# SCH_sensor-de-n_vel_2026-06-17.net
KiCad netlist of a schematic drawn in EasyEDA
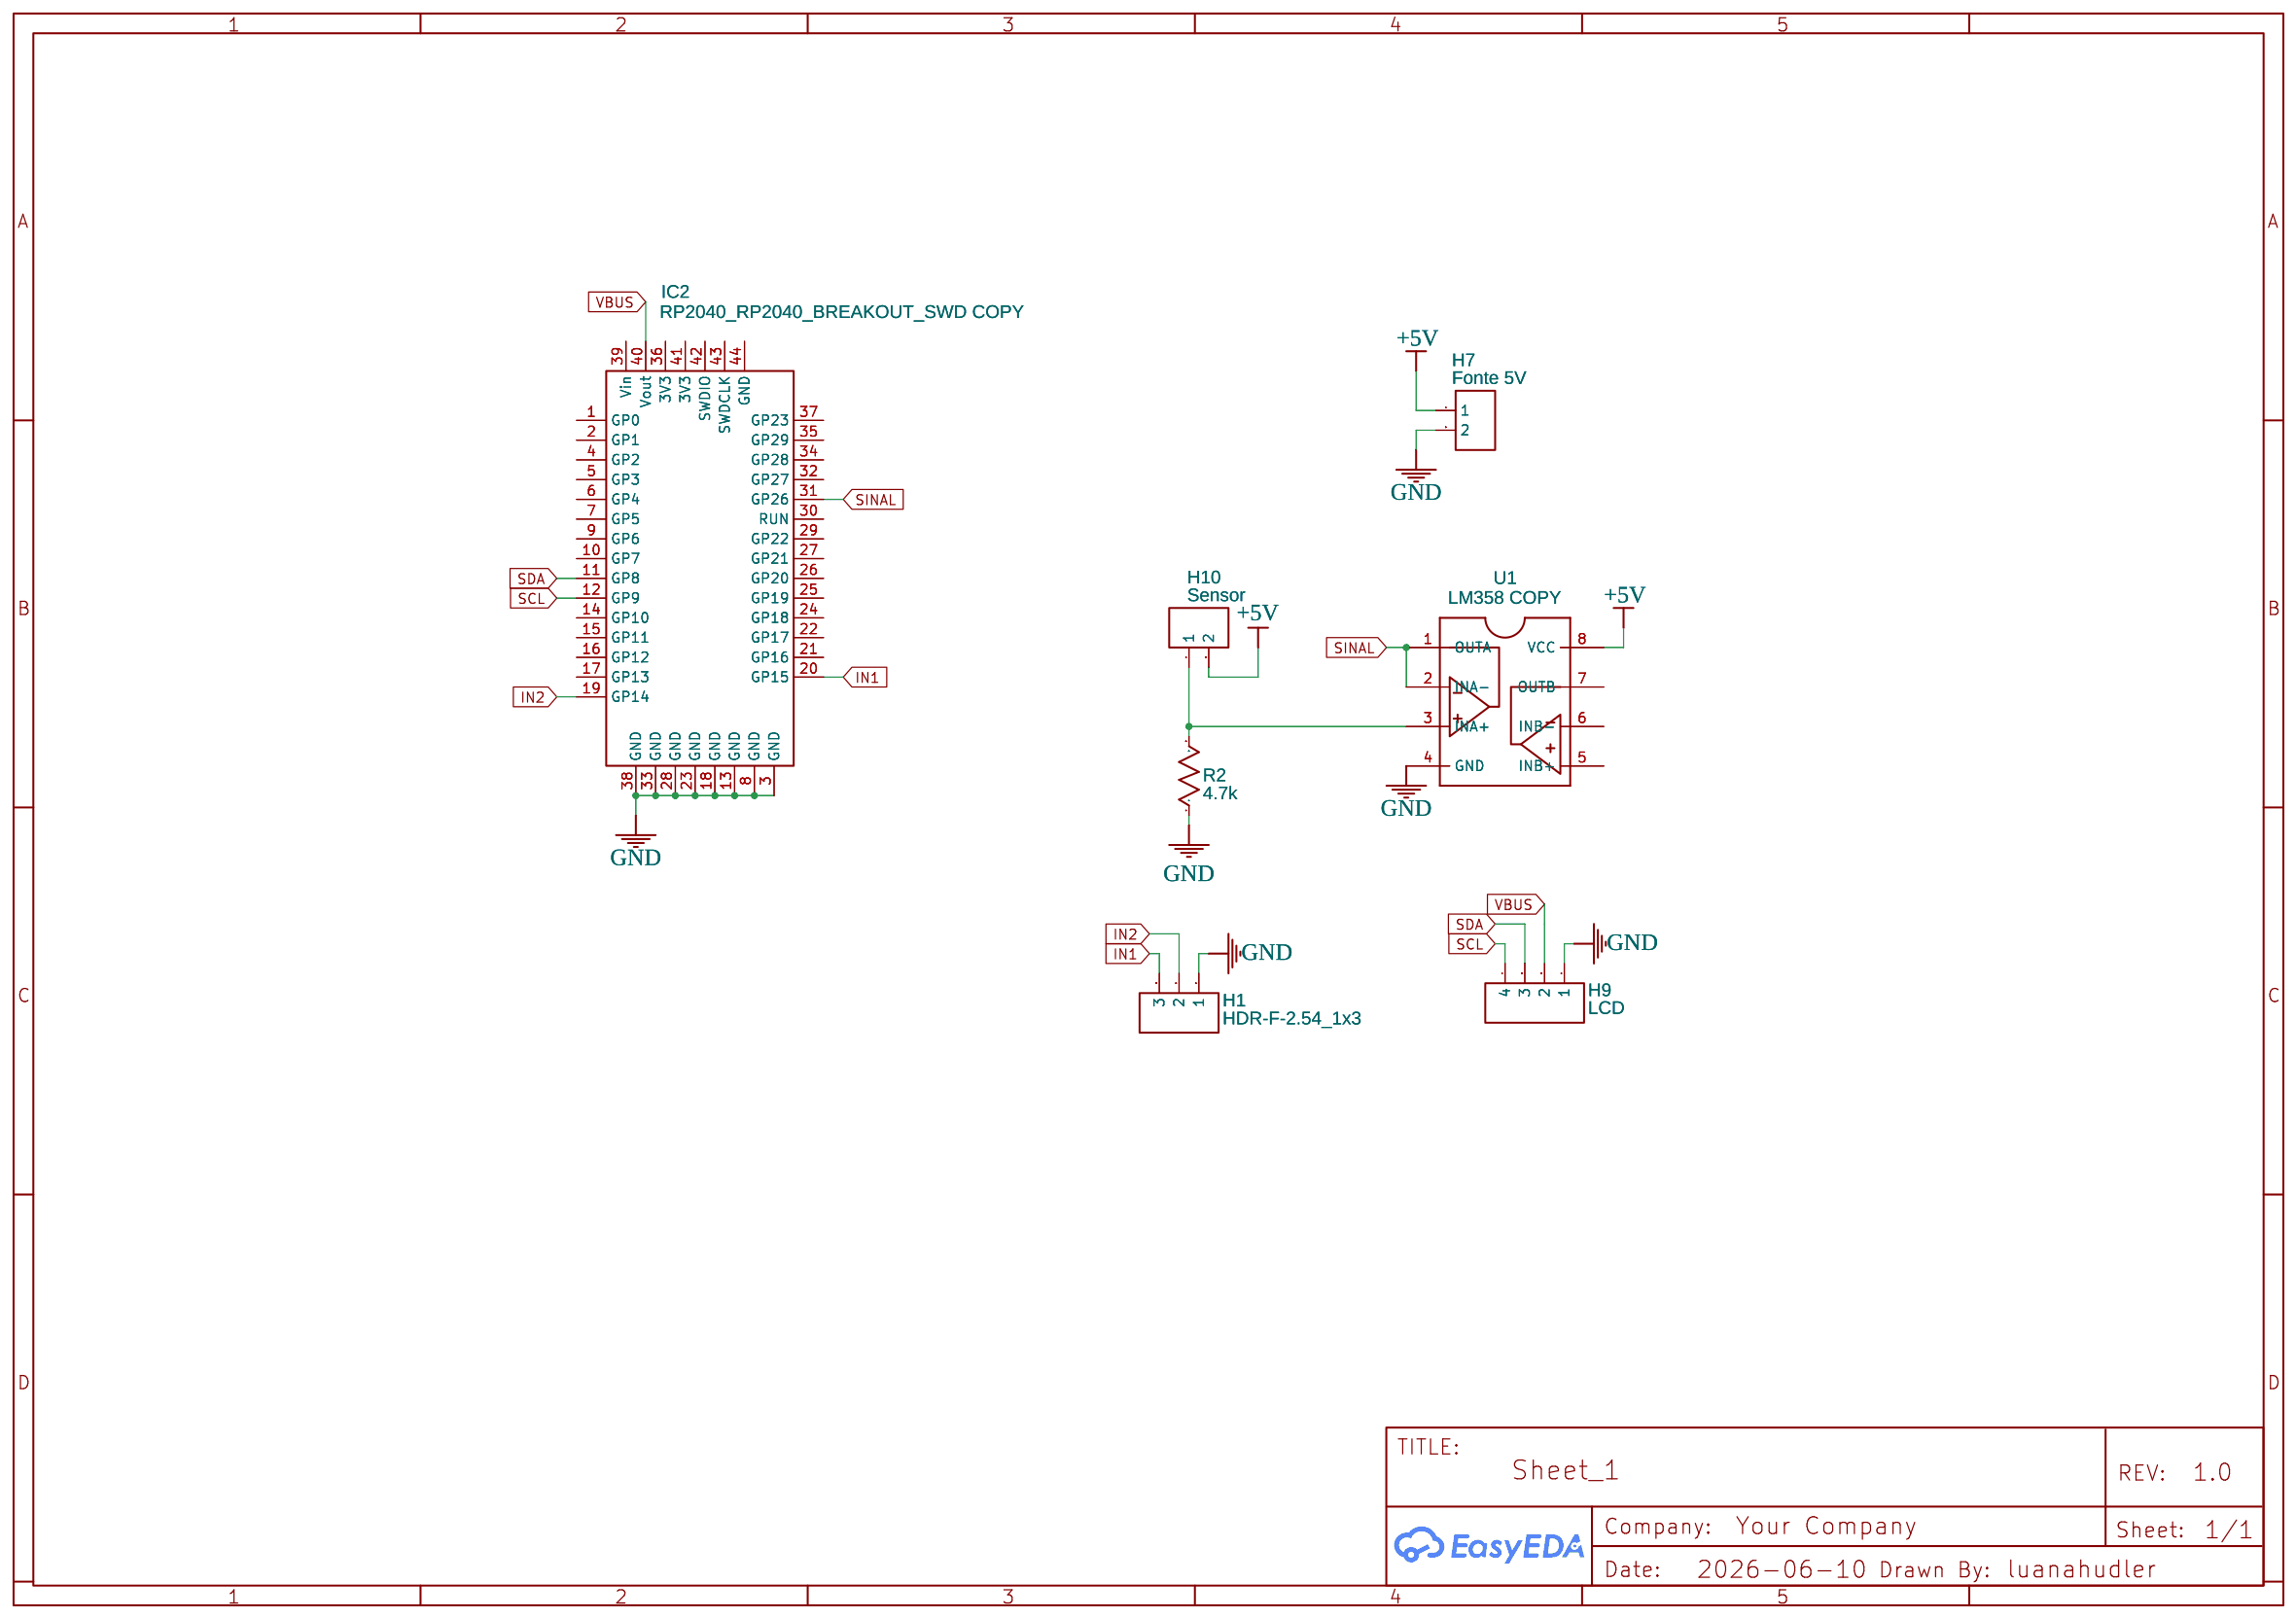
[diagram p0: schematic sheet]

(export (version "E")
  (design (tool "Eeschema 10.0.6"))
  (components
    (comp (ref "H1") (value "HDR-F-2.54_1x3") (libsource (lib "") (part "HDR-F-2.54_1x3")))
    (comp (ref "H7") (value "Fonte 5V") (libsource (lib "") (part "HDR-F-2.54_1x2")))
    (comp (ref "H9") (value "LCD") (libsource (lib "") (part "HDR-F-2.54_1x4")))
    (comp (ref "H10") (value "Sensor") (libsource (lib "") (part "HDR-F-2.54_1x2_1")))
    (comp (ref "IC2")
      (value "RP2040_RP2040_BREAKOUT_SWD COPY")
      (libsource (lib "") (part "RP2040_RP2040_BREAKOUT_SWD COPY"))
    )
    (comp (ref "R2") (value "4.7k") (libsource (lib "") (part "R_AXIAL-0.3_US")))
    (comp (ref "U1")
      (value "LM358 COPY")
      (fields (field (name "Manufacturer Part") "TI") (field (name "Manufacturer") "LM358MX/NOPB"))
      (libsource (lib "") (part "LM358 COPY"))
    )
  )
  (nets
    (net (code "1") (name "+5V") (class "Default")
      (node (ref "H10") (pin "2") (pinfunction "2_2") (pintype "input"))
      (node (ref "H7") (pin "1") (pinfunction "1_1") (pintype "input"))
      (node (ref "U1") (pin "8") (pinfunction "VCC_8") (pintype "unspecified"))
    )
    (net (code "2") (name "GND") (class "Default")
      (node (ref "H1") (pin "1") (pinfunction "1_1") (pintype "input"))
      (node (ref "H7") (pin "2") (pinfunction "2_2") (pintype "input"))
      (node (ref "H9") (pin "1") (pinfunction "1_1") (pintype "unspecified"))
      (node (ref "IC2") (pin "13") (pinfunction "GND_13") (pintype "unspecified"))
      (node (ref "IC2") (pin "18") (pinfunction "GND_18") (pintype "unspecified"))
      (node (ref "IC2") (pin "23") (pinfunction "GND_23") (pintype "unspecified"))
      (node (ref "IC2") (pin "28") (pinfunction "GND_28") (pintype "unspecified"))
      (node (ref "IC2") (pin "3") (pinfunction "GND_3") (pintype "unspecified"))
      (node (ref "IC2") (pin "33") (pinfunction "GND_33") (pintype "unspecified"))
      (node (ref "IC2") (pin "38") (pinfunction "GND_38") (pintype "unspecified"))
      (node (ref "IC2") (pin "8") (pinfunction "GND_8") (pintype "unspecified"))
      (node (ref "R2") (pin "1") (pinfunction "1_1") (pintype "unspecified"))
      (node (ref "U1") (pin "4") (pinfunction "GND_4") (pintype "unspecified"))
    )
    (net (code "3") (name "IN1") (class "Default")
      (node (ref "H1") (pin "3") (pinfunction "3_3") (pintype "input"))
      (node (ref "IC2") (pin "20") (pinfunction "GP15_20") (pintype "unspecified"))
    )
    (net (code "4") (name "IN2") (class "Default")
      (node (ref "H1") (pin "2") (pinfunction "2_2") (pintype "input"))
      (node (ref "IC2") (pin "19") (pinfunction "GP14_19") (pintype "unspecified"))
    )
    (net (code "5") (name "Net-(U1-INA+)") (class "Default")
      (node (ref "H10") (pin "1") (pinfunction "1_1") (pintype "input"))
      (node (ref "R2") (pin "2") (pinfunction "2_2") (pintype "unspecified"))
      (node (ref "U1") (pin "3") (pinfunction "INA+_3") (pintype "unspecified"))
    )
    (net (code "6") (name "SCL") (class "Default")
      (node (ref "H9") (pin "4") (pinfunction "4_4") (pintype "unspecified"))
      (node (ref "IC2") (pin "12") (pinfunction "GP9_12") (pintype "unspecified"))
    )
    (net (code "7") (name "SDA") (class "Default")
      (node (ref "H9") (pin "3") (pinfunction "3_3") (pintype "unspecified"))
      (node (ref "IC2") (pin "11") (pinfunction "GP8_11") (pintype "unspecified"))
    )
    (net (code "8") (name "SINAL") (class "Default")
      (node (ref "IC2") (pin "31") (pinfunction "GP26_31") (pintype "unspecified"))
      (node (ref "U1") (pin "1") (pinfunction "OUTA_1") (pintype "output"))
      (node (ref "U1") (pin "2") (pinfunction "INA-_2") (pintype "unspecified"))
    )
    (net (code "9") (name "VBUS") (class "Default")
      (node (ref "H9") (pin "2") (pinfunction "2_2") (pintype "unspecified"))
      (node (ref "IC2") (pin "40") (pinfunction "Vout_40") (pintype "unspecified"))
    )
    (net (code "10") (name "unconnected-(IC2-3V3-Pad36)") (class "Default")
      (node (ref "IC2") (pin "36") (pinfunction "3V3_36") (pintype "unspecified"))
    )
    (net (code "11") (name "unconnected-(IC2-3V3-Pad41)") (class "Default")
      (node (ref "IC2") (pin "41") (pinfunction "3V3_41") (pintype "unspecified"))
    )
    (net (code "12") (name "unconnected-(IC2-GND-Pad44)") (class "Default")
      (node (ref "IC2") (pin "44") (pinfunction "GND_44") (pintype "unspecified"))
    )
    (net (code "13") (name "unconnected-(IC2-GP0-Pad1)") (class "Default")
      (node (ref "IC2") (pin "1") (pinfunction "GP0_1") (pintype "unspecified"))
    )
    (net (code "14") (name "unconnected-(IC2-GP1-Pad2)") (class "Default")
      (node (ref "IC2") (pin "2") (pinfunction "GP1_2") (pintype "unspecified"))
    )
    (net (code "15") (name "unconnected-(IC2-GP2-Pad4)") (class "Default")
      (node (ref "IC2") (pin "4") (pinfunction "GP2_4") (pintype "unspecified"))
    )
    (net (code "16") (name "unconnected-(IC2-GP3-Pad5)") (class "Default")
      (node (ref "IC2") (pin "5") (pinfunction "GP3_5") (pintype "unspecified"))
    )
    (net (code "17") (name "unconnected-(IC2-GP4-Pad6)") (class "Default")
      (node (ref "IC2") (pin "6") (pinfunction "GP4_6") (pintype "unspecified"))
    )
    (net (code "18") (name "unconnected-(IC2-GP5-Pad7)") (class "Default")
      (node (ref "IC2") (pin "7") (pinfunction "GP5_7") (pintype "unspecified"))
    )
    (net (code "19") (name "unconnected-(IC2-GP6-Pad9)") (class "Default")
      (node (ref "IC2") (pin "9") (pinfunction "GP6_9") (pintype "unspecified"))
    )
    (net (code "20") (name "unconnected-(IC2-GP7-Pad10)") (class "Default")
      (node (ref "IC2") (pin "10") (pinfunction "GP7_10") (pintype "unspecified"))
    )
    (net (code "21") (name "unconnected-(IC2-GP10-Pad14)") (class "Default")
      (node (ref "IC2") (pin "14") (pinfunction "GP10_14") (pintype "unspecified"))
    )
    (net (code "22") (name "unconnected-(IC2-GP11-Pad15)") (class "Default")
      (node (ref "IC2") (pin "15") (pinfunction "GP11_15") (pintype "unspecified"))
    )
    (net (code "23") (name "unconnected-(IC2-GP12-Pad16)") (class "Default")
      (node (ref "IC2") (pin "16") (pinfunction "GP12_16") (pintype "unspecified"))
    )
    (net (code "24") (name "unconnected-(IC2-GP13-Pad17)") (class "Default")
      (node (ref "IC2") (pin "17") (pinfunction "GP13_17") (pintype "unspecified"))
    )
    (net (code "25") (name "unconnected-(IC2-GP16-Pad21)") (class "Default")
      (node (ref "IC2") (pin "21") (pinfunction "GP16_21") (pintype "unspecified"))
    )
    (net (code "26") (name "unconnected-(IC2-GP17-Pad22)") (class "Default")
      (node (ref "IC2") (pin "22") (pinfunction "GP17_22") (pintype "unspecified"))
    )
    (net (code "27") (name "unconnected-(IC2-GP18-Pad24)") (class "Default")
      (node (ref "IC2") (pin "24") (pinfunction "GP18_24") (pintype "unspecified"))
    )
    (net (code "28") (name "unconnected-(IC2-GP19-Pad25)") (class "Default")
      (node (ref "IC2") (pin "25") (pinfunction "GP19_25") (pintype "unspecified"))
    )
    (net (code "29") (name "unconnected-(IC2-GP20-Pad26)") (class "Default")
      (node (ref "IC2") (pin "26") (pinfunction "GP20_26") (pintype "unspecified"))
    )
    (net (code "30") (name "unconnected-(IC2-GP21-Pad27)") (class "Default")
      (node (ref "IC2") (pin "27") (pinfunction "GP21_27") (pintype "unspecified"))
    )
    (net (code "31") (name "unconnected-(IC2-GP22-Pad29)") (class "Default")
      (node (ref "IC2") (pin "29") (pinfunction "GP22_29") (pintype "unspecified"))
    )
    (net (code "32") (name "unconnected-(IC2-GP23-Pad37)") (class "Default")
      (node (ref "IC2") (pin "37") (pinfunction "GP23_37") (pintype "unspecified"))
    )
    (net (code "33") (name "unconnected-(IC2-GP27-Pad32)") (class "Default")
      (node (ref "IC2") (pin "32") (pinfunction "GP27_32") (pintype "unspecified"))
    )
    (net (code "34") (name "unconnected-(IC2-GP28-Pad34)") (class "Default")
      (node (ref "IC2") (pin "34") (pinfunction "GP28_34") (pintype "unspecified"))
    )
    (net (code "35") (name "unconnected-(IC2-GP29-Pad35)") (class "Default")
      (node (ref "IC2") (pin "35") (pinfunction "GP29_35") (pintype "unspecified"))
    )
    (net (code "36") (name "unconnected-(IC2-RUN-Pad30)") (class "Default")
      (node (ref "IC2") (pin "30") (pinfunction "RUN_30") (pintype "unspecified"))
    )
    (net (code "37") (name "unconnected-(IC2-SWDCLK-Pad43)") (class "Default")
      (node (ref "IC2") (pin "43") (pinfunction "SWDCLK_43") (pintype "unspecified"))
    )
    (net (code "38") (name "unconnected-(IC2-SWDIO-Pad42)") (class "Default")
      (node (ref "IC2") (pin "42") (pinfunction "SWDIO_42") (pintype "unspecified"))
    )
    (net (code "39") (name "unconnected-(IC2-Vin-Pad39)") (class "Default")
      (node (ref "IC2") (pin "39") (pinfunction "Vin_39") (pintype "unspecified"))
    )
    (net (code "40") (name "unconnected-(U1-INB+-Pad5)") (class "Default")
      (node (ref "U1") (pin "5") (pinfunction "INB+_5") (pintype "unspecified"))
    )
    (net (code "41") (name "unconnected-(U1-INB--Pad6)") (class "Default")
      (node (ref "U1") (pin "6") (pinfunction "INB-_6") (pintype "unspecified"))
    )
    (net (code "42") (name "unconnected-(U1-OUTB-Pad7)") (class "Default")
      (node (ref "U1") (pin "7") (pinfunction "OUTB_7") (pintype "unspecified"))
    )
  )
)
